# Interface.net
KiCad netlist of a schematic drawn in EAGLE
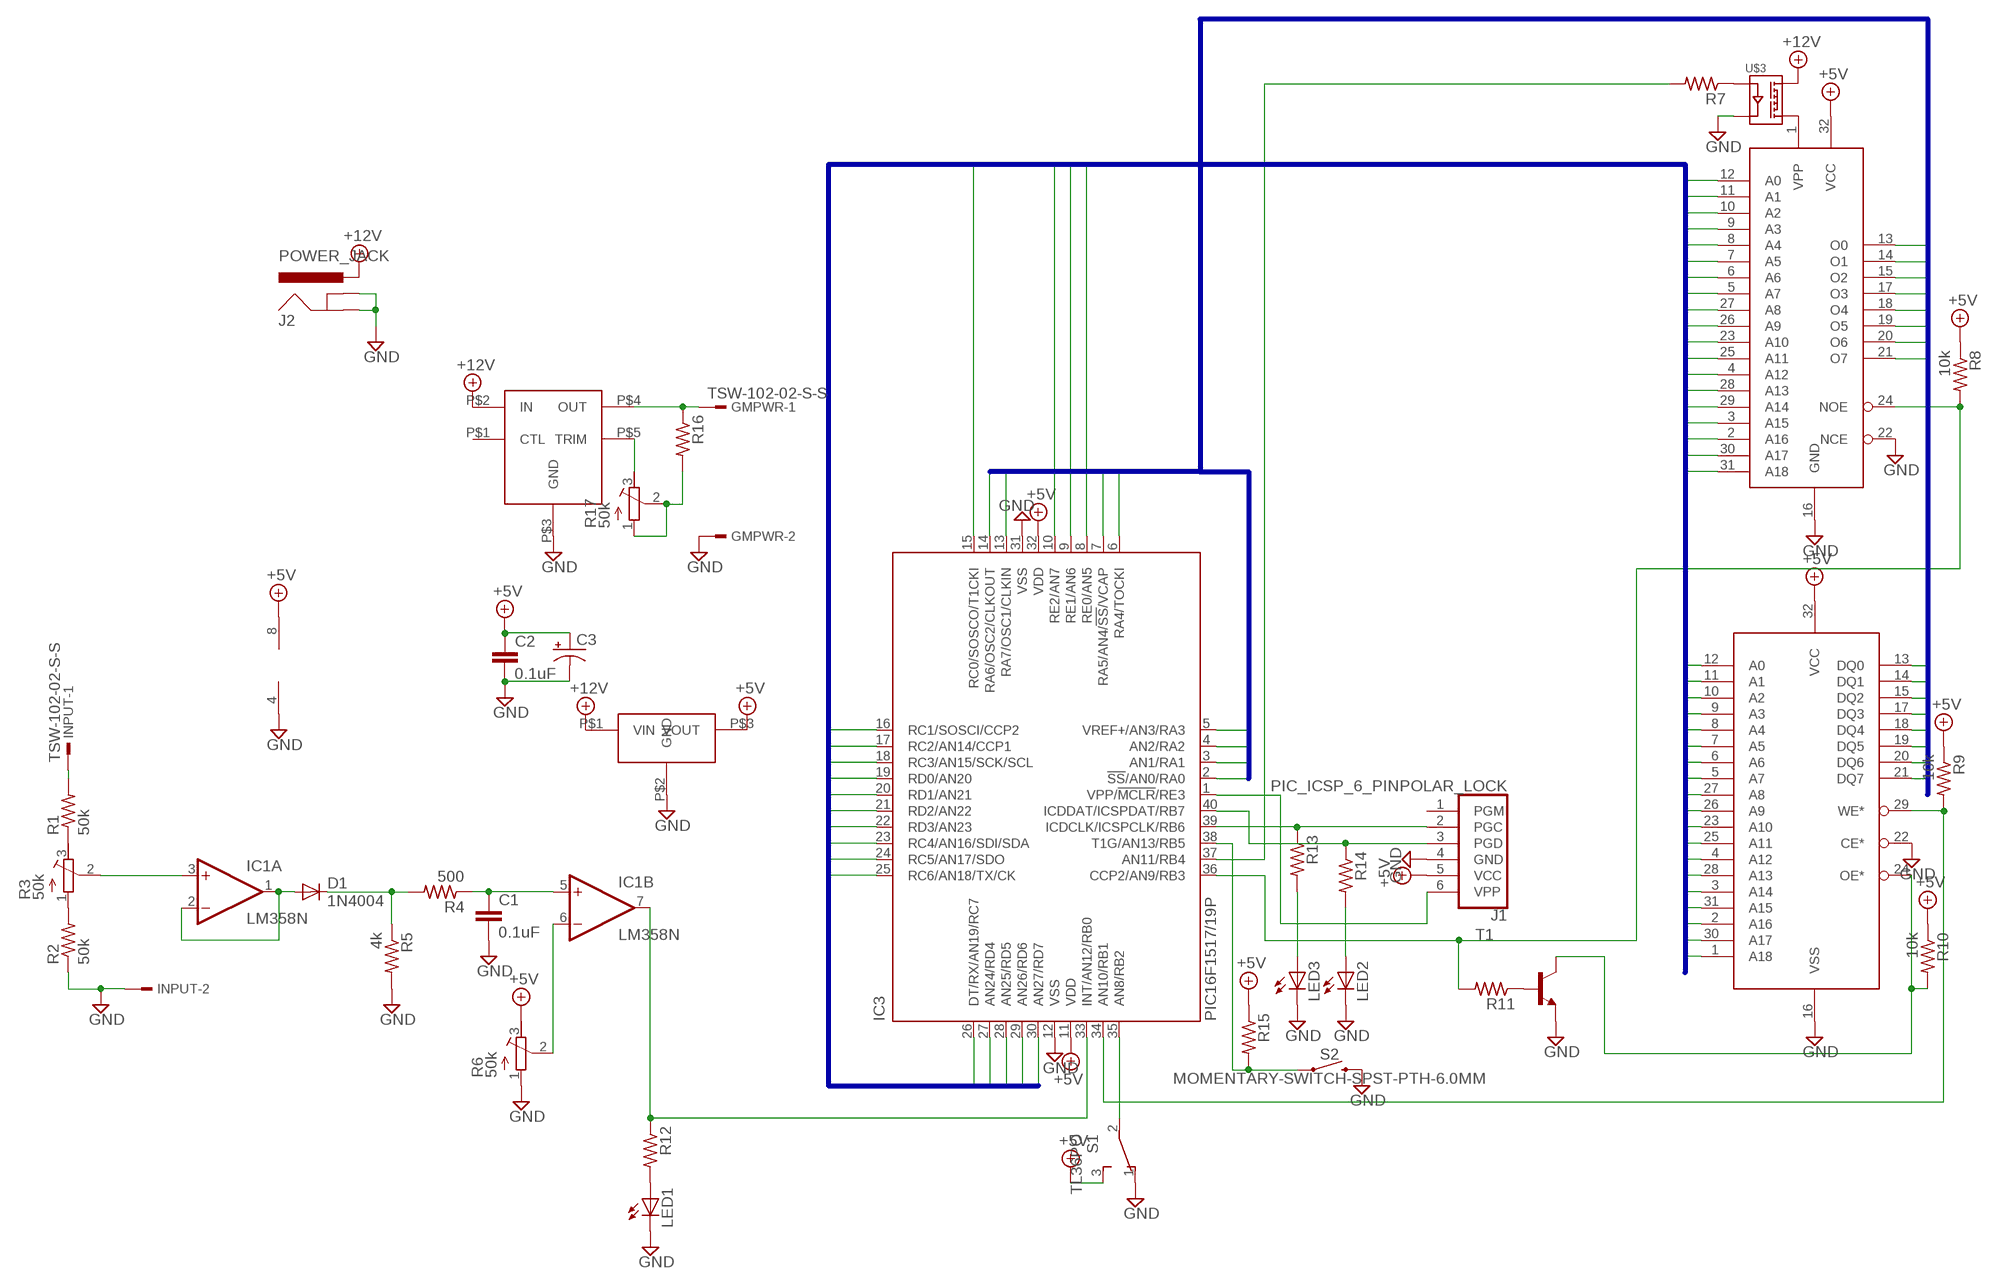
[diagram p0: schematic, sheet 1]

(export (version "E")
  (design (tool "Eeschema 10.0.6"))
  (components
    (comp (ref "C1")
      (value "0.1uF")
      (footprint "eagle-import:C050-025X075")
      (libsource (lib "eagle-import") (part "C-EU050-025X075"))
    )
    (comp (ref "C2")
      (value "0.1uF")
      (footprint "eagle-import:C050-025X075")
      (libsource (lib "eagle-import") (part "C-EU050-025X075"))
    )
    (comp (ref "C3")
      (value "CPOL-USE5-8.5")
      (footprint "eagle-import:E5-8,5")
      (libsource (lib "eagle-import") (part "CPOL-USE5-8.5"))
    )
    (comp (ref "D1")
      (value "1N4004")
      (footprint "eagle-import:DO41-10")
      (libsource (lib "eagle-import") (part "1N4004"))
    )
    (comp (ref "GMPWR")
      (value "TSW-102-02-S-S")
      (footprint "eagle-import:TSW-102-02-S-S")
      (libsource (lib "eagle-import") (part "TSW-102-02-S-S"))
    )
    (comp (ref "IC1")
      (value "LM358N")
      (footprint "eagle-import:DIL08")
      (libsource (lib "eagle-import") (part "LM358N"))
    )
    (comp (ref "IC3")
      (value "PIC16F1517/19P")
      (footprint "eagle-import:DIL40")
      (libsource (lib "eagle-import") (part "PIC16F1517/19P"))
    )
    (comp (ref "INPUT")
      (value "TSW-102-02-S-S")
      (footprint "eagle-import:TSW-102-02-S-S")
      (libsource (lib "eagle-import") (part "TSW-102-02-S-S"))
    )
    (comp (ref "J1")
      (value "PIC_ICSP_6_PINPOLAR_LOCK")
      (footprint "eagle-import:MOLEX-1X6_LOCK")
      (libsource (lib "eagle-import") (part "PIC_ICSP_6_PINPOLAR_LOCK"))
    )
    (comp (ref "J2")
      (value "POWER_JACK")
      (footprint "eagle-import:POWER_JACK_PTH")
      (libsource (lib "eagle-import") (part "POWER_JACK"))
    )
    (comp (ref "LED1")
      (value "LED3MM")
      (footprint "eagle-import:LED3MM")
      (libsource (lib "eagle-import") (part "LED3MM"))
    )
    (comp (ref "LED2")
      (value "LED3MM")
      (footprint "eagle-import:LED3MM")
      (libsource (lib "eagle-import") (part "LED3MM"))
    )
    (comp (ref "LED3")
      (value "LED3MM")
      (footprint "eagle-import:LED3MM")
      (libsource (lib "eagle-import") (part "LED3MM"))
    )
    (comp (ref "R1")
      (value "50k")
      (footprint "eagle-import:0204V")
      (libsource (lib "eagle-import") (part "R-US_0204/2V"))
    )
    (comp (ref "R2")
      (value "50k")
      (footprint "eagle-import:0204V")
      (libsource (lib "eagle-import") (part "R-US_0204/2V"))
    )
    (comp (ref "R3")
      (value "50k")
      (footprint "eagle-import:RTRIM3296W")
      (libsource (lib "eagle-import") (part "R-TRIMM3296W"))
    )
    (comp (ref "R4")
      (value "500")
      (footprint "eagle-import:0204V")
      (libsource (lib "eagle-import") (part "R-US_0204/2V"))
    )
    (comp (ref "R5")
      (value "4k")
      (footprint "eagle-import:0204V")
      (libsource (lib "eagle-import") (part "R-US_0204/2V"))
    )
    (comp (ref "R6")
      (value "50k")
      (footprint "eagle-import:RTRIM3296W")
      (libsource (lib "eagle-import") (part "R-TRIMM3296W"))
    )
    (comp (ref "R7")
      (value "R-US_0204/2V")
      (footprint "eagle-import:0204V")
      (libsource (lib "eagle-import") (part "R-US_0204/2V"))
    )
    (comp (ref "R8")
      (value "10k")
      (footprint "eagle-import:0204V")
      (libsource (lib "eagle-import") (part "R-US_0204/2V"))
    )
    (comp (ref "R9")
      (value "10k")
      (footprint "eagle-import:0204V")
      (libsource (lib "eagle-import") (part "R-US_0204/2V"))
    )
    (comp (ref "R10")
      (value "10k")
      (footprint "eagle-import:0204V")
      (libsource (lib "eagle-import") (part "R-US_0204/2V"))
    )
    (comp (ref "R11")
      (value "R-US_0204/2V")
      (footprint "eagle-import:0204V")
      (libsource (lib "eagle-import") (part "R-US_0204/2V"))
    )
    (comp (ref "R12")
      (value "R-US_0204/2V")
      (footprint "eagle-import:0204V")
      (libsource (lib "eagle-import") (part "R-US_0204/2V"))
    )
    (comp (ref "R13")
      (value "R-US_0204/2V")
      (footprint "eagle-import:0204V")
      (libsource (lib "eagle-import") (part "R-US_0204/2V"))
    )
    (comp (ref "R14")
      (value "R-US_0204/2V")
      (footprint "eagle-import:0204V")
      (libsource (lib "eagle-import") (part "R-US_0204/2V"))
    )
    (comp (ref "R15")
      (value "R-US_0204/2V")
      (footprint "eagle-import:0204V")
      (libsource (lib "eagle-import") (part "R-US_0204/2V"))
    )
    (comp (ref "R16")
      (value "R-US_0204/2V")
      (footprint "eagle-import:0204V")
      (libsource (lib "eagle-import") (part "R-US_0204/2V"))
    )
    (comp (ref "R17")
      (value "50k")
      (footprint "eagle-import:RTRIM3296W")
      (libsource (lib "eagle-import") (part "R-TRIMM3296W"))
    )
    (comp (ref "S1")
      (value "TL36PO")
      (footprint "eagle-import:TL3XPO")
      (libsource (lib "eagle-import") (part "TL36PO"))
    )
    (comp (ref "S2")
      (value "MOMENTARY-SWITCH-SPST-PTH-6.0MM")
      (footprint "eagle-import:TACTILE_SWITCH_PTH_6.0MM")
      (libsource (lib "eagle-import") (part "MOMENTARY-SWITCH-SPST-PTH-6.0MM"))
    )
    (comp (ref "T1")
      (value "MPS2222A-NPN-TO92-CBE")
      (footprint "eagle-import:TO92-CBE")
      (libsource (lib "eagle-import") (part "-NPN-TO92-CBEMPS2222A"))
    )
    (comp (ref "U$1")
      (value "AT27C040")
      (footprint "eagle-import:DIL32")
      (libsource (lib "eagle-import") (part "AT27C040"))
    )
    (comp (ref "U$2")
      (value "AS6C4008")
      (footprint "eagle-import:DIL32")
      (libsource (lib "eagle-import") (part "AS6C4008"))
    )
    (comp (ref "U$3")
      (value "CPC1008N")
      (footprint "eagle-import:SOP04")
      (libsource (lib "eagle-import") (part "CPC1008N"))
    )
    (comp (ref "U$4")
      (value "OKR-T/1.5-W12-C")
      (footprint "eagle-import:SIP5")
      (libsource (lib "eagle-import") (part "OKR-T"))
    )
    (comp (ref "U$5")
      (value "OKI-78SR-5/1.5-W36-C")
      (footprint "eagle-import:SIP_PS")
      (libsource (lib "eagle-import") (part "OKI-78SR-5/1.5-W36-C"))
    )
  )
  (nets
    (net (code "1") (name "+5V") (class "Default")
      (node (ref "C2") (pin "1") (pinfunction "1_1") (pintype "passive"))
      (node (ref "C3") (pin "+") (pinfunction "+_+") (pintype "passive"))
      (node (ref "IC1") (pin "8") (pinfunction "V+_8") (pintype "power_in"))
      (node (ref "IC3") (pin "11") (pinfunction "VDD_11") (pintype "power_in"))
      (node (ref "IC3") (pin "32") (pinfunction "VDD_32") (pintype "power_in"))
      (node (ref "J1") (pin "5") (pinfunction "VCC_5") (pintype "power_in"))
      (node (ref "R10") (pin "1") (pinfunction "1_1") (pintype "passive"))
      (node (ref "R15") (pin "1") (pinfunction "1_1") (pintype "passive"))
      (node (ref "R6") (pin "3") (pinfunction "E_3") (pintype "passive"))
      (node (ref "R8") (pin "1") (pinfunction "1_1") (pintype "passive"))
      (node (ref "R9") (pin "1") (pinfunction "1_1") (pintype "passive"))
      (node (ref "S1") (pin "3") (pinfunction "S_3") (pintype "passive"))
      (node (ref "U$1") (pin "32") (pinfunction "VCC_32") (pintype "bidirectional"))
      (node (ref "U$2") (pin "32") (pinfunction "VCC_32") (pintype "bidirectional"))
      (node (ref "U$5") (pin "P$3") (pinfunction "VOUT_P$3") (pintype "bidirectional"))
    )
    (net (code "2") (name "+12V") (class "Default")
      (node (ref "J2") (pin "PWR") (pinfunction "PWR_PWR") (pintype "bidirectional"))
      (node (ref "U$3") (pin "4") (pinfunction "DC_4") (pintype "bidirectional"))
      (node (ref "U$4") (pin "P$2") (pinfunction "IN_P$2") (pintype "bidirectional"))
      (node (ref "U$5") (pin "P$1") (pinfunction "VIN_P$1") (pintype "bidirectional"))
    )
    (net (code "3") (name "/A0") (class "Default")
      (node (ref "IC3") (pin "15") (pinfunction "RC0/SOSCO/T1CKI_15") (pintype "bidirectional"))
      (node (ref "U$1") (pin "12") (pinfunction "A0_12") (pintype "bidirectional"))
      (node (ref "U$2") (pin "12") (pinfunction "A0_12") (pintype "bidirectional"))
    )
    (net (code "4") (name "/A1") (class "Default")
      (node (ref "IC3") (pin "16") (pinfunction "RC1/SOSCI/CCP2_16") (pintype "bidirectional"))
      (node (ref "U$1") (pin "11") (pinfunction "A1_11") (pintype "bidirectional"))
      (node (ref "U$2") (pin "11") (pinfunction "A1_11") (pintype "bidirectional"))
    )
    (net (code "5") (name "/A2") (class "Default")
      (node (ref "IC3") (pin "17") (pinfunction "RC2/AN14/CCP1_17") (pintype "bidirectional"))
      (node (ref "U$1") (pin "10") (pinfunction "A2_10") (pintype "bidirectional"))
      (node (ref "U$2") (pin "10") (pinfunction "A2_10") (pintype "bidirectional"))
    )
    (net (code "6") (name "/A3") (class "Default")
      (node (ref "IC3") (pin "18") (pinfunction "RC3/AN15/SCK/SCL_18") (pintype "bidirectional"))
      (node (ref "U$1") (pin "9") (pinfunction "A3_9") (pintype "bidirectional"))
      (node (ref "U$2") (pin "9") (pinfunction "A3_9") (pintype "bidirectional"))
    )
    (net (code "7") (name "/A4") (class "Default")
      (node (ref "IC3") (pin "23") (pinfunction "RC4/AN16/SDI/SDA_23") (pintype "bidirectional"))
      (node (ref "U$1") (pin "8") (pinfunction "A4_8") (pintype "bidirectional"))
      (node (ref "U$2") (pin "8") (pinfunction "A4_8") (pintype "bidirectional"))
    )
    (net (code "8") (name "/A5") (class "Default")
      (node (ref "IC3") (pin "24") (pinfunction "RC5/AN17/SDO_24") (pintype "bidirectional"))
      (node (ref "U$1") (pin "7") (pinfunction "A5_7") (pintype "bidirectional"))
      (node (ref "U$2") (pin "7") (pinfunction "A5_7") (pintype "bidirectional"))
    )
    (net (code "9") (name "/A6") (class "Default")
      (node (ref "IC3") (pin "25") (pinfunction "RC6/AN18/TX/CK_25") (pintype "bidirectional"))
      (node (ref "U$1") (pin "6") (pinfunction "A6_6") (pintype "bidirectional"))
      (node (ref "U$2") (pin "6") (pinfunction "A6_6") (pintype "bidirectional"))
    )
    (net (code "10") (name "/A7") (class "Default")
      (node (ref "IC3") (pin "26") (pinfunction "DT/RX/AN19/RC7_26") (pintype "bidirectional"))
      (node (ref "U$1") (pin "5") (pinfunction "A7_5") (pintype "bidirectional"))
      (node (ref "U$2") (pin "5") (pinfunction "A7_5") (pintype "bidirectional"))
    )
    (net (code "11") (name "/A8") (class "Default")
      (node (ref "IC3") (pin "19") (pinfunction "RD0/AN20_19") (pintype "bidirectional"))
      (node (ref "U$1") (pin "27") (pinfunction "A8_27") (pintype "bidirectional"))
      (node (ref "U$2") (pin "27") (pinfunction "A8_27") (pintype "bidirectional"))
    )
    (net (code "12") (name "/A9") (class "Default")
      (node (ref "IC3") (pin "20") (pinfunction "RD1/AN21_20") (pintype "bidirectional"))
      (node (ref "U$1") (pin "26") (pinfunction "A9_26") (pintype "bidirectional"))
      (node (ref "U$2") (pin "26") (pinfunction "A9_26") (pintype "bidirectional"))
    )
    (net (code "13") (name "/A10") (class "Default")
      (node (ref "IC3") (pin "21") (pinfunction "RD2/AN22_21") (pintype "bidirectional"))
      (node (ref "U$1") (pin "23") (pinfunction "A10_23") (pintype "bidirectional"))
      (node (ref "U$2") (pin "23") (pinfunction "A10_23") (pintype "bidirectional"))
    )
    (net (code "14") (name "/A11") (class "Default")
      (node (ref "IC3") (pin "22") (pinfunction "RD3/AN23_22") (pintype "bidirectional"))
      (node (ref "U$1") (pin "25") (pinfunction "A11_25") (pintype "bidirectional"))
      (node (ref "U$2") (pin "25") (pinfunction "A11_25") (pintype "bidirectional"))
    )
    (net (code "15") (name "/A12") (class "Default")
      (node (ref "IC3") (pin "27") (pinfunction "AN24/RD4_27") (pintype "bidirectional"))
      (node (ref "U$1") (pin "4") (pinfunction "A12_4") (pintype "bidirectional"))
      (node (ref "U$2") (pin "4") (pinfunction "A12_4") (pintype "bidirectional"))
    )
    (net (code "16") (name "/A13") (class "Default")
      (node (ref "IC3") (pin "28") (pinfunction "AN25/RD5_28") (pintype "bidirectional"))
      (node (ref "U$1") (pin "28") (pinfunction "A13_28") (pintype "bidirectional"))
      (node (ref "U$2") (pin "28") (pinfunction "A13_28") (pintype "bidirectional"))
    )
    (net (code "17") (name "/A14") (class "Default")
      (node (ref "IC3") (pin "29") (pinfunction "AN26/RD6_29") (pintype "bidirectional"))
      (node (ref "U$1") (pin "29") (pinfunction "A14_29") (pintype "bidirectional"))
      (node (ref "U$2") (pin "3") (pinfunction "A14_3") (pintype "bidirectional"))
    )
    (net (code "18") (name "/A15") (class "Default")
      (node (ref "IC3") (pin "30") (pinfunction "AN27/RD7_30") (pintype "bidirectional"))
      (node (ref "U$1") (pin "3") (pinfunction "A15_3") (pintype "bidirectional"))
      (node (ref "U$2") (pin "31") (pinfunction "A15_31") (pintype "bidirectional"))
    )
    (net (code "19") (name "/A16") (class "Default")
      (node (ref "IC3") (pin "8") (pinfunction "RE0/AN5_8") (pintype "bidirectional"))
      (node (ref "U$1") (pin "2") (pinfunction "A16_2") (pintype "bidirectional"))
      (node (ref "U$2") (pin "2") (pinfunction "A16_2") (pintype "bidirectional"))
    )
    (net (code "20") (name "/A17") (class "Default")
      (node (ref "IC3") (pin "9") (pinfunction "RE1/AN6_9") (pintype "bidirectional"))
      (node (ref "U$1") (pin "30") (pinfunction "A17_30") (pintype "bidirectional"))
      (node (ref "U$2") (pin "30") (pinfunction "A17_30") (pintype "bidirectional"))
    )
    (net (code "21") (name "/A18") (class "Default")
      (node (ref "IC3") (pin "10") (pinfunction "RE2/AN7_10") (pintype "bidirectional"))
      (node (ref "U$1") (pin "31") (pinfunction "A18_31") (pintype "bidirectional"))
      (node (ref "U$2") (pin "1") (pinfunction "A18_1") (pintype "bidirectional"))
    )
    (net (code "22") (name "/D0") (class "Default")
      (node (ref "IC3") (pin "2") (pinfunction "~{SS}/AN0/RA0_2") (pintype "bidirectional"))
      (node (ref "U$1") (pin "13") (pinfunction "O0_13") (pintype "output"))
      (node (ref "U$2") (pin "13") (pinfunction "DQ0_13") (pintype "bidirectional"))
    )
    (net (code "23") (name "/D1") (class "Default")
      (node (ref "IC3") (pin "3") (pinfunction "AN1/RA1_3") (pintype "bidirectional"))
      (node (ref "U$1") (pin "14") (pinfunction "O1_14") (pintype "output"))
      (node (ref "U$2") (pin "14") (pinfunction "DQ1_14") (pintype "bidirectional"))
    )
    (net (code "24") (name "/D2") (class "Default")
      (node (ref "IC3") (pin "4") (pinfunction "AN2/RA2_4") (pintype "bidirectional"))
      (node (ref "U$1") (pin "15") (pinfunction "O2_15") (pintype "output"))
      (node (ref "U$2") (pin "15") (pinfunction "DQ2_15") (pintype "bidirectional"))
    )
    (net (code "25") (name "/D3") (class "Default")
      (node (ref "IC3") (pin "5") (pinfunction "VREF+/AN3/RA3_5") (pintype "bidirectional"))
      (node (ref "U$1") (pin "17") (pinfunction "O3_17") (pintype "output"))
      (node (ref "U$2") (pin "17") (pinfunction "DQ3_17") (pintype "bidirectional"))
    )
    (net (code "26") (name "/D4") (class "Default")
      (node (ref "IC3") (pin "6") (pinfunction "RA4/TOCKI_6") (pintype "bidirectional"))
      (node (ref "U$1") (pin "18") (pinfunction "O4_18") (pintype "output"))
      (node (ref "U$2") (pin "18") (pinfunction "DQ4_18") (pintype "bidirectional"))
    )
    (net (code "27") (name "/D5") (class "Default")
      (node (ref "IC3") (pin "7") (pinfunction "RA5/AN4/~{SS}/VCAP_7") (pintype "bidirectional"))
      (node (ref "U$1") (pin "19") (pinfunction "O5_19") (pintype "output"))
      (node (ref "U$2") (pin "19") (pinfunction "DQ5_19") (pintype "bidirectional"))
    )
    (net (code "28") (name "/D6") (class "Default")
      (node (ref "IC3") (pin "14") (pinfunction "RA6/OSC2/CLKOUT_14") (pintype "bidirectional"))
      (node (ref "U$1") (pin "20") (pinfunction "O6_20") (pintype "output"))
      (node (ref "U$2") (pin "20") (pinfunction "DQ6_20") (pintype "bidirectional"))
    )
    (net (code "29") (name "/D7") (class "Default")
      (node (ref "IC3") (pin "13") (pinfunction "RA7/OSC1/CLKIN_13") (pintype "bidirectional"))
      (node (ref "U$1") (pin "21") (pinfunction "O7_21") (pintype "output"))
      (node (ref "U$2") (pin "21") (pinfunction "DQ7_21") (pintype "bidirectional"))
    )
    (net (code "30") (name "GND") (class "Default")
      (node (ref "C1") (pin "2") (pinfunction "2_2") (pintype "passive"))
      (node (ref "C2") (pin "2") (pinfunction "2_2") (pintype "passive"))
      (node (ref "C3") (pin "-") (pinfunction "-_-") (pintype "passive"))
      (node (ref "GMPWR") (pin "2") (pinfunction "1_2") (pintype "passive"))
      (node (ref "IC1") (pin "4") (pinfunction "V-_4") (pintype "power_in"))
      (node (ref "IC3") (pin "12") (pinfunction "VSS_12") (pintype "power_in"))
      (node (ref "IC3") (pin "31") (pinfunction "VSS_31") (pintype "power_in"))
      (node (ref "INPUT") (pin "2") (pinfunction "1_2") (pintype "passive"))
      (node (ref "J1") (pin "4") (pinfunction "GND_4") (pintype "power_in"))
      (node (ref "J2") (pin "GND") (pinfunction "GND_GND") (pintype "bidirectional"))
      (node (ref "J2") (pin "GNDBREAK") (pinfunction "GNDBREAK_GNDBREAK") (pintype "bidirectional"))
      (node (ref "LED1") (pin "K") (pinfunction "C_K") (pintype "passive"))
      (node (ref "LED2") (pin "K") (pinfunction "C_K") (pintype "passive"))
      (node (ref "LED3") (pin "K") (pinfunction "C_K") (pintype "passive"))
      (node (ref "R2") (pin "1") (pinfunction "1_1") (pintype "passive"))
      (node (ref "R5") (pin "2") (pinfunction "2_2") (pintype "passive"))
      (node (ref "R6") (pin "1") (pinfunction "A_1") (pintype "passive"))
      (node (ref "S1") (pin "1") (pinfunction "O_1") (pintype "passive"))
      (node (ref "S2") (pin "3") (pinfunction "2_3") (pintype "passive"))
      (node (ref "T1") (pin "E") (pinfunction "E_E") (pintype "passive"))
      (node (ref "U$1") (pin "16") (pinfunction "GND_16") (pintype "bidirectional"))
      (node (ref "U$1") (pin "22") (pinfunction "NCE_22") (pintype "bidirectional"))
      (node (ref "U$2") (pin "16") (pinfunction "VSS_16") (pintype "bidirectional"))
      (node (ref "U$2") (pin "22") (pinfunction "CE*_22") (pintype "bidirectional"))
      (node (ref "U$3") (pin "3") (pinfunction "IN-_3") (pintype "power_in"))
      (node (ref "U$4") (pin "P$3") (pinfunction "GND_P$3") (pintype "bidirectional"))
      (node (ref "U$5") (pin "P$2") (pinfunction "GND_P$2") (pintype "bidirectional"))
    )
    (net (code "31") (name "Net-(D1-PadC)") (class "Default")
      (node (ref "D1") (pin "C") (pinfunction "C_C") (pintype "passive"))
      (node (ref "R4") (pin "2") (pinfunction "2_2") (pintype "passive"))
      (node (ref "R5") (pin "1") (pinfunction "1_1") (pintype "passive"))
    )
    (net (code "32") (name "Net-(IC1A-+IN)") (class "Default")
      (node (ref "IC1") (pin "3") (pinfunction "+IN_3") (pintype "input"))
      (node (ref "R3") (pin "2") (pinfunction "S_2") (pintype "passive"))
    )
    (net (code "33") (name "Net-(IC1A--IN)") (class "Default")
      (node (ref "D1") (pin "A") (pinfunction "A_A") (pintype "passive"))
      (node (ref "IC1") (pin "1") (pinfunction "OUT_1") (pintype "output"))
      (node (ref "IC1") (pin "2") (pinfunction "-IN_2") (pintype "input"))
    )
    (net (code "34") (name "Net-(IC1B-+IN)") (class "Default")
      (node (ref "C1") (pin "1") (pinfunction "1_1") (pintype "passive"))
      (node (ref "IC1") (pin "5") (pinfunction "+IN_5") (pintype "input"))
      (node (ref "R4") (pin "1") (pinfunction "1_1") (pintype "passive"))
    )
    (net (code "35") (name "Net-(IC1B--IN)") (class "Default")
      (node (ref "IC1") (pin "6") (pinfunction "-IN_6") (pintype "input"))
      (node (ref "R6") (pin "2") (pinfunction "S_2") (pintype "passive"))
    )
    (net (code "36") (name "Net-(IC1B-OUT)") (class "Default")
      (node (ref "IC1") (pin "7") (pinfunction "OUT_7") (pintype "output"))
      (node (ref "IC3") (pin "33") (pinfunction "INT/AN12/RB0_33") (pintype "bidirectional"))
      (node (ref "R12") (pin "1") (pinfunction "1_1") (pintype "passive"))
    )
    (net (code "37") (name "Net-(IC3-AN8{slash}RB2)") (class "Default")
      (node (ref "IC3") (pin "35") (pinfunction "AN8/RB2_35") (pintype "bidirectional"))
      (node (ref "S1") (pin "2") (pinfunction "P_2") (pintype "passive"))
    )
    (net (code "38") (name "Net-(IC3-AN10{slash}RB1)") (class "Default")
      (node (ref "IC3") (pin "34") (pinfunction "AN10/RB1_34") (pintype "bidirectional"))
      (node (ref "R9") (pin "2") (pinfunction "2_2") (pintype "passive"))
      (node (ref "U$2") (pin "29") (pinfunction "WE*_29") (pintype "bidirectional"))
    )
    (net (code "39") (name "Net-(IC3-AN11{slash}RB4)") (class "Default")
      (node (ref "IC3") (pin "37") (pinfunction "AN11/RB4_37") (pintype "bidirectional"))
      (node (ref "R7") (pin "2") (pinfunction "2_2") (pintype "passive"))
    )
    (net (code "40") (name "Net-(IC3-CCP2{slash}AN9{slash}RB3)") (class "Default")
      (node (ref "IC3") (pin "36") (pinfunction "CCP2/AN9/RB3_36") (pintype "bidirectional"))
      (node (ref "R11") (pin "2") (pinfunction "2_2") (pintype "passive"))
      (node (ref "R8") (pin "2") (pinfunction "2_2") (pintype "passive"))
      (node (ref "U$1") (pin "24") (pinfunction "NOE_24") (pintype "bidirectional"))
    )
    (net (code "41") (name "Net-(IC3-ICDCLK{slash}ICSPCLK{slash}RB6)") (class "Default")
      (node (ref "IC3") (pin "39") (pinfunction "ICDCLK/ICSPCLK/RB6_39") (pintype "bidirectional"))
      (node (ref "J1") (pin "2") (pinfunction "PGC_2") (pintype "bidirectional"))
      (node (ref "R13") (pin "1") (pinfunction "1_1") (pintype "passive"))
    )
    (net (code "42") (name "Net-(IC3-ICDDAT{slash}ICSPDAT{slash}RB7)") (class "Default")
      (node (ref "IC3") (pin "40") (pinfunction "ICDDAT/ICSPDAT/RB7_40") (pintype "bidirectional"))
      (node (ref "J1") (pin "3") (pinfunction "PGD_3") (pintype "bidirectional"))
      (node (ref "R14") (pin "1") (pinfunction "1_1") (pintype "passive"))
    )
    (net (code "43") (name "Net-(IC3-T1G{slash}AN13{slash}RB5)") (class "Default")
      (node (ref "IC3") (pin "38") (pinfunction "T1G/AN13/RB5_38") (pintype "bidirectional"))
      (node (ref "R15") (pin "2") (pinfunction "2_2") (pintype "passive"))
      (node (ref "S2") (pin "1") (pinfunction "1_1") (pintype "passive"))
    )
    (net (code "44") (name "Net-(IC3-VPP{slash}~{MCLR}{slash}RE3)") (class "Default")
      (node (ref "IC3") (pin "1") (pinfunction "VPP/~{MCLR}/RE3_1") (pintype "input"))
      (node (ref "J1") (pin "6") (pinfunction "VPP_6") (pintype "bidirectional"))
    )
    (net (code "45") (name "Net-(INPUT-Pad1)") (class "Default")
      (node (ref "INPUT") (pin "1") (pinfunction "1_1") (pintype "passive"))
      (node (ref "R1") (pin "2") (pinfunction "2_2") (pintype "passive"))
    )
    (net (code "46") (name "Net-(LED1-PadA)") (class "Default")
      (node (ref "LED1") (pin "A") (pinfunction "A_A") (pintype "passive"))
      (node (ref "R12") (pin "2") (pinfunction "2_2") (pintype "passive"))
    )
    (net (code "47") (name "Net-(LED2-PadA)") (class "Default")
      (node (ref "LED2") (pin "A") (pinfunction "A_A") (pintype "passive"))
      (node (ref "R14") (pin "2") (pinfunction "2_2") (pintype "passive"))
    )
    (net (code "48") (name "Net-(LED3-PadA)") (class "Default")
      (node (ref "LED3") (pin "A") (pinfunction "A_A") (pintype "passive"))
      (node (ref "R13") (pin "2") (pinfunction "2_2") (pintype "passive"))
    )
    (net (code "49") (name "Net-(R3-A)") (class "Default")
      (node (ref "R2") (pin "2") (pinfunction "2_2") (pintype "passive"))
      (node (ref "R3") (pin "1") (pinfunction "A_1") (pintype "passive"))
    )
    (net (code "50") (name "Net-(R3-E)") (class "Default")
      (node (ref "R1") (pin "1") (pinfunction "1_1") (pintype "passive"))
      (node (ref "R3") (pin "3") (pinfunction "E_3") (pintype "passive"))
    )
    (net (code "51") (name "Net-(R11-Pad1)") (class "Default")
      (node (ref "R11") (pin "1") (pinfunction "1_1") (pintype "passive"))
      (node (ref "T1") (pin "B") (pinfunction "B_B") (pintype "passive"))
    )
    (net (code "52") (name "Net-(R17-A)") (class "Default")
      (node (ref "R16") (pin "2") (pinfunction "2_2") (pintype "passive"))
      (node (ref "R17") (pin "1") (pinfunction "A_1") (pintype "passive"))
      (node (ref "R17") (pin "2") (pinfunction "S_2") (pintype "passive"))
    )
    (net (code "53") (name "Net-(R17-E)") (class "Default")
      (node (ref "R17") (pin "3") (pinfunction "E_3") (pintype "passive"))
      (node (ref "U$4") (pin "P$5") (pinfunction "TRIM_P$5") (pintype "bidirectional"))
    )
    (net (code "54") (name "Net-(U$1-VPP)") (class "Default")
      (node (ref "U$1") (pin "1") (pinfunction "VPP_1") (pintype "bidirectional"))
      (node (ref "U$3") (pin "6") (pinfunction "DC_6") (pintype "bidirectional"))
    )
    (net (code "55") (name "Net-(U$2-OE*)") (class "Default")
      (node (ref "R10") (pin "2") (pinfunction "2_2") (pintype "passive"))
      (node (ref "T1") (pin "C") (pinfunction "C_C") (pintype "passive"))
      (node (ref "U$2") (pin "24") (pinfunction "OE*_24") (pintype "bidirectional"))
    )
    (net (code "56") (name "Net-(U$3-IN+)") (class "Default")
      (node (ref "R7") (pin "1") (pinfunction "1_1") (pintype "passive"))
      (node (ref "U$3") (pin "1") (pinfunction "IN+_1") (pintype "input"))
    )
    (net (code "57") (name "Net-(U$4-OUT)") (class "Default")
      (node (ref "GMPWR") (pin "1") (pinfunction "1_1") (pintype "passive"))
      (node (ref "R16") (pin "1") (pinfunction "1_1") (pintype "passive"))
      (node (ref "U$4") (pin "P$4") (pinfunction "OUT_P$4") (pintype "bidirectional"))
    )
    (net (code "58") (name "unconnected-(J1-PGM-Pad1)") (class "Default")
      (node (ref "J1") (pin "1") (pinfunction "PGM_1") (pintype "bidirectional"))
    )
    (net (code "59") (name "unconnected-(U$4-CTL-PadP$1)") (class "Default")
      (node (ref "U$4") (pin "P$1") (pinfunction "CTL_P$1") (pintype "bidirectional"))
    )
  )
)
